# ADC.net
KiCad netlist of a schematic drawn in Altium Designer
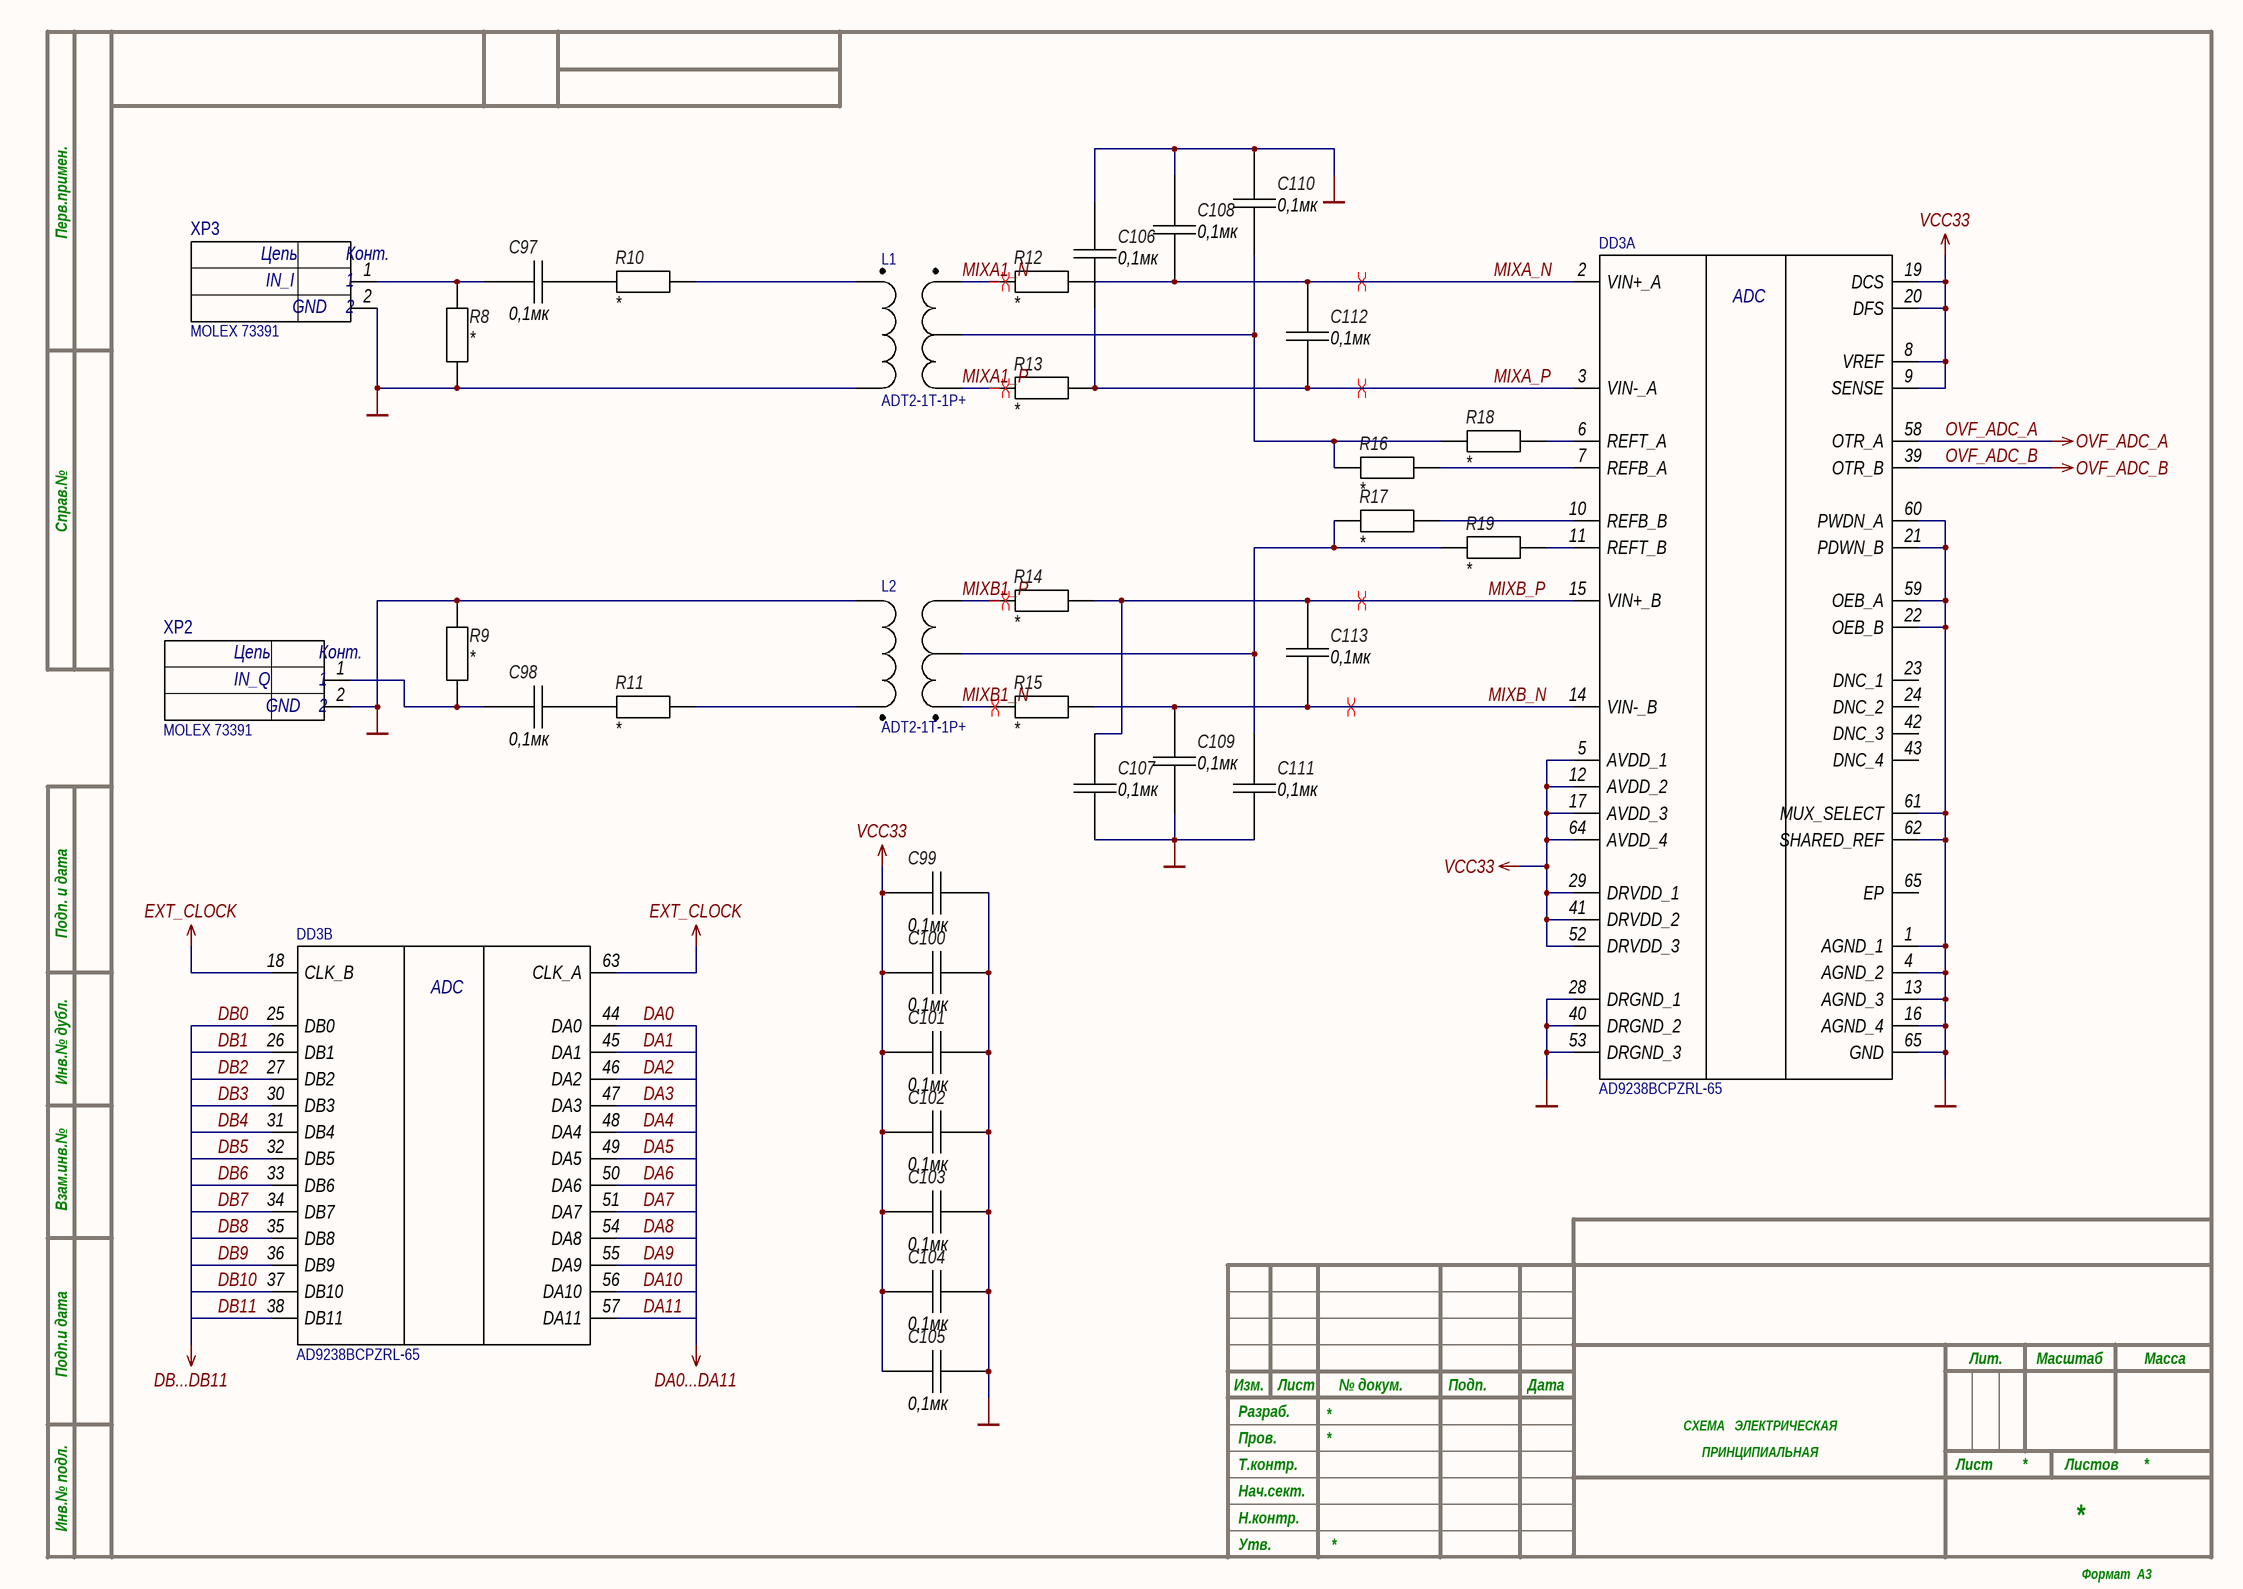
[diagram p0: ADC.SchDoc]

(export (version "E")
  (design (tool "Eeschema 10.0.6"))
  (components
    (comp (ref "C97")
      (value "0,1мк")
      (footprint "0603")
      (libsource (lib "FPGA_Automotibe_Radar_Lib") (part "Capacitor_0603"))
    )
    (comp (ref "C98")
      (value "0,1мк")
      (footprint "0603")
      (libsource (lib "FPGA_Automotibe_Radar_Lib") (part "Capacitor_0603"))
    )
    (comp (ref "C99")
      (value "0,1мк")
      (footprint "RESC1005X35N")
      (libsource (lib "FPGA_Automotibe_Radar_Lib") (part "Capacitor_0.1u"))
    )
    (comp (ref "C100")
      (value "0,1мк")
      (footprint "RESC1005X35N")
      (libsource (lib "FPGA_Automotibe_Radar_Lib") (part "Capacitor_0.1u"))
    )
    (comp (ref "C101")
      (value "0,1мк")
      (footprint "RESC1005X35N")
      (libsource (lib "FPGA_Automotibe_Radar_Lib") (part "Capacitor_0.1u"))
    )
    (comp (ref "C102")
      (value "0,1мк")
      (footprint "RESC1005X35N")
      (libsource (lib "FPGA_Automotibe_Radar_Lib") (part "Capacitor_0.1u"))
    )
    (comp (ref "C103")
      (value "0,1мк")
      (footprint "RESC1005X35N")
      (libsource (lib "FPGA_Automotibe_Radar_Lib") (part "Capacitor_0.1u"))
    )
    (comp (ref "C104")
      (value "0,1мк")
      (footprint "RESC1005X35N")
      (libsource (lib "FPGA_Automotibe_Radar_Lib") (part "Capacitor_0.1u"))
    )
    (comp (ref "C105")
      (value "0,1мк")
      (footprint "RESC1005X35N")
      (libsource (lib "FPGA_Automotibe_Radar_Lib") (part "Capacitor_0.1u"))
    )
    (comp (ref "C106")
      (value "0,1мк")
      (footprint "0603")
      (libsource (lib "FPGA_Automotibe_Radar_Lib") (part "Capacitor_0603"))
    )
    (comp (ref "C107")
      (value "0,1мк")
      (footprint "0603")
      (libsource (lib "FPGA_Automotibe_Radar_Lib") (part "Capacitor_0603"))
    )
    (comp (ref "C108")
      (value "0,1мк")
      (footprint "0603")
      (libsource (lib "FPGA_Automotibe_Radar_Lib") (part "Capacitor_0603"))
    )
    (comp (ref "C109")
      (value "0,1мк")
      (footprint "0603")
      (libsource (lib "FPGA_Automotibe_Radar_Lib") (part "Capacitor_0603"))
    )
    (comp (ref "C110")
      (value "0,1мк")
      (footprint "0603")
      (libsource (lib "FPGA_Automotibe_Radar_Lib") (part "Capacitor_0603"))
    )
    (comp (ref "C111")
      (value "0,1мк")
      (footprint "0603")
      (libsource (lib "FPGA_Automotibe_Radar_Lib") (part "Capacitor_0603"))
    )
    (comp (ref "C112")
      (value "0,1мк")
      (footprint "RESC1005X35N")
      (libsource (lib "FPGA_Automotibe_Radar_Lib") (part "Capacitor_0.1u"))
    )
    (comp (ref "C113")
      (value "0,1мк")
      (footprint "RESC1005X35N")
      (libsource (lib "FPGA_Automotibe_Radar_Lib") (part "Capacitor_0.1u"))
    )
    (comp (ref "DD3")
      (value "AD9238BCPZRL-65")
      (footprint "QFN50P900X900X80-65N-D")
      (libsource (lib "FPGA_Automotibe_Radar_Lib") (part "ADC"))
    )
    (comp (ref "L1") (value "ADT2-1T-1P+") (footprint "ADT1517") (libsource (lib "") (part "TRANSFORMER_1")))
    (comp (ref "L2")
      (value "ADT2-1T-1P+")
      (footprint "ADT1517")
      (libsource (lib "FPGA_Automotibe_Radar_Lib") (part "TRANSFORMER"))
    )
    (comp (ref "R8")
      (value "*")
      (footprint "RESC3216X75N")
      (fields
        (field (name "TOLERANCE") "5%")
        (field (name "POWER") "0,1 Вт")
        (field (name "VALUEMANUFACTURERPARTNUMBER") "RC0603JR-07680RL")
      )
      (libsource (lib "FPGA_Automotibe_Radar_Lib") (part "Resistor"))
    )
    (comp (ref "R9")
      (value "*")
      (footprint "RESC3216X75N")
      (fields
        (field (name "TOLERANCE") "5%")
        (field (name "POWER") "0,1 Вт")
        (field (name "VALUEMANUFACTURERPARTNUMBER") "RC0603JR-07680RL")
      )
      (libsource (lib "FPGA_Automotibe_Radar_Lib") (part "Resistor"))
    )
    (comp (ref "R10")
      (value "*")
      (footprint "RESC3216X75N")
      (fields
        (field (name "TOLERANCE") "5%")
        (field (name "POWER") "0,1 Вт")
        (field (name "VALUEMANUFACTURERPARTNUMBER") "RC0603JR-07680RL")
      )
      (libsource (lib "FPGA_Automotibe_Radar_Lib") (part "Resistor"))
    )
    (comp (ref "R11")
      (value "*")
      (footprint "RESC3216X75N")
      (fields
        (field (name "TOLERANCE") "5%")
        (field (name "POWER") "0,1 Вт")
        (field (name "VALUEMANUFACTURERPARTNUMBER") "RC0603JR-07680RL")
      )
      (libsource (lib "FPGA_Automotibe_Radar_Lib") (part "Resistor"))
    )
    (comp (ref "R12")
      (value "*")
      (footprint "RESC3216X75N")
      (fields
        (field (name "TOLERANCE") "5%")
        (field (name "POWER") "0,1 Вт")
        (field (name "VALUEMANUFACTURERPARTNUMBER") "RC0603JR-07680RL")
      )
      (libsource (lib "FPGA_Automotibe_Radar_Lib") (part "Resistor"))
    )
    (comp (ref "R13")
      (value "*")
      (footprint "RESC3216X75N")
      (fields
        (field (name "TOLERANCE") "5%")
        (field (name "POWER") "0,1 Вт")
        (field (name "VALUEMANUFACTURERPARTNUMBER") "RC0603JR-07680RL")
      )
      (libsource (lib "FPGA_Automotibe_Radar_Lib") (part "Resistor"))
    )
    (comp (ref "R14")
      (value "*")
      (footprint "RESC3216X75N")
      (fields
        (field (name "TOLERANCE") "5%")
        (field (name "POWER") "0,1 Вт")
        (field (name "VALUEMANUFACTURERPARTNUMBER") "RC0603JR-07680RL")
      )
      (libsource (lib "FPGA_Automotibe_Radar_Lib") (part "Resistor"))
    )
    (comp (ref "R15")
      (value "*")
      (footprint "RESC3216X75N")
      (fields
        (field (name "TOLERANCE") "5%")
        (field (name "POWER") "0,1 Вт")
        (field (name "VALUEMANUFACTURERPARTNUMBER") "RC0603JR-07680RL")
      )
      (libsource (lib "FPGA_Automotibe_Radar_Lib") (part "Resistor"))
    )
    (comp (ref "R16")
      (value "*")
      (footprint "RESC3216X75N")
      (fields
        (field (name "TOLERANCE") "5%")
        (field (name "POWER") "0,1 Вт")
        (field (name "VALUEMANUFACTURERPARTNUMBER") "RC0603JR-07680RL")
      )
      (libsource (lib "FPGA_Automotibe_Radar_Lib") (part "Resistor_0402_1k"))
    )
    (comp (ref "R17")
      (value "*")
      (footprint "RESC3216X75N")
      (fields
        (field (name "TOLERANCE") "5%")
        (field (name "POWER") "0,1 Вт")
        (field (name "VALUEMANUFACTURERPARTNUMBER") "RC0603JR-07680RL")
      )
      (libsource (lib "FPGA_Automotibe_Radar_Lib") (part "Resistor_0402_1k"))
    )
    (comp (ref "R18")
      (value "*")
      (footprint "RESC3216X75N")
      (fields
        (field (name "TOLERANCE") "5%")
        (field (name "POWER") "0,1 Вт")
        (field (name "VALUEMANUFACTURERPARTNUMBER") "RC0603JR-07680RL")
      )
      (libsource (lib "FPGA_Automotibe_Radar_Lib") (part "Resistor_0402_1k"))
    )
    (comp (ref "R19")
      (value "*")
      (footprint "RESC3216X75N")
      (fields
        (field (name "TOLERANCE") "5%")
        (field (name "POWER") "0,1 Вт")
        (field (name "VALUEMANUFACTURERPARTNUMBER") "RC0603JR-07680RL")
      )
      (libsource (lib "FPGA_Automotibe_Radar_Lib") (part "Resistor_0402_1k"))
    )
    (comp (ref "XP2")
      (value "MOLEX 73391")
      (footprint "CONN_73391-0070_MOL")
      (libsource (lib "FPGA_Automotibe_Radar_Lib") (part "SMA_REAL"))
    )
    (comp (ref "XP3")
      (value "MOLEX 73391")
      (footprint "CONN_73391-0070_MOL")
      (libsource (lib "FPGA_Automotibe_Radar_Lib") (part "SMA_REAL"))
    )
  )
  (nets
    (net (code "1") (name "/DA0") (class "Default")
      (node (ref "DD3") (pin "44") (pinfunction "DA0_44") (pintype "passive"))
    )
    (net (code "2") (name "/DA1") (class "Default")
      (node (ref "DD3") (pin "45") (pinfunction "DA1_45") (pintype "passive"))
    )
    (net (code "3") (name "/DA2") (class "Default")
      (node (ref "DD3") (pin "46") (pinfunction "DA2_46") (pintype "passive"))
    )
    (net (code "4") (name "/DA3") (class "Default")
      (node (ref "DD3") (pin "47") (pinfunction "DA3_47") (pintype "passive"))
    )
    (net (code "5") (name "/DA4") (class "Default")
      (node (ref "DD3") (pin "48") (pinfunction "DA4_48") (pintype "passive"))
    )
    (net (code "6") (name "/DA5") (class "Default")
      (node (ref "DD3") (pin "49") (pinfunction "DA5_49") (pintype "passive"))
    )
    (net (code "7") (name "/DA6") (class "Default")
      (node (ref "DD3") (pin "50") (pinfunction "DA6_50") (pintype "passive"))
    )
    (net (code "8") (name "/DA7") (class "Default")
      (node (ref "DD3") (pin "51") (pinfunction "DA7_51") (pintype "passive"))
    )
    (net (code "9") (name "/DA8") (class "Default")
      (node (ref "DD3") (pin "54") (pinfunction "DA8_54") (pintype "passive"))
    )
    (net (code "10") (name "/DA9") (class "Default")
      (node (ref "DD3") (pin "55") (pinfunction "DA9_55") (pintype "passive"))
    )
    (net (code "11") (name "/DA10") (class "Default")
      (node (ref "DD3") (pin "56") (pinfunction "DA10_56") (pintype "passive"))
    )
    (net (code "12") (name "/DA11") (class "Default")
      (node (ref "DD3") (pin "57") (pinfunction "DA11_57") (pintype "passive"))
    )
    (net (code "13") (name "/DB0") (class "Default")
      (node (ref "DD3") (pin "25") (pinfunction "DB0_25") (pintype "passive"))
    )
    (net (code "14") (name "/DB1") (class "Default")
      (node (ref "DD3") (pin "26") (pinfunction "DB1_26") (pintype "passive"))
    )
    (net (code "15") (name "/DB2") (class "Default")
      (node (ref "DD3") (pin "27") (pinfunction "DB2_27") (pintype "passive"))
    )
    (net (code "16") (name "/DB3") (class "Default")
      (node (ref "DD3") (pin "30") (pinfunction "DB3_30") (pintype "passive"))
    )
    (net (code "17") (name "/DB4") (class "Default")
      (node (ref "DD3") (pin "31") (pinfunction "DB4_31") (pintype "passive"))
    )
    (net (code "18") (name "/DB5") (class "Default")
      (node (ref "DD3") (pin "32") (pinfunction "DB5_32") (pintype "passive"))
    )
    (net (code "19") (name "/DB6") (class "Default")
      (node (ref "DD3") (pin "33") (pinfunction "DB6_33") (pintype "passive"))
    )
    (net (code "20") (name "/DB7") (class "Default")
      (node (ref "DD3") (pin "34") (pinfunction "DB7_34") (pintype "passive"))
    )
    (net (code "21") (name "/DB8") (class "Default")
      (node (ref "DD3") (pin "35") (pinfunction "DB8_35") (pintype "passive"))
    )
    (net (code "22") (name "/DB9") (class "Default")
      (node (ref "DD3") (pin "36") (pinfunction "DB9_36") (pintype "passive"))
    )
    (net (code "23") (name "/DB10") (class "Default")
      (node (ref "DD3") (pin "37") (pinfunction "DB10_37") (pintype "passive"))
    )
    (net (code "24") (name "/DB11") (class "Default")
      (node (ref "DD3") (pin "38") (pinfunction "DB11_38") (pintype "passive"))
    )
    (net (code "25") (name "/MIXA1_N") (class "Default")
      (node (ref "L1") (pin "6") (pinfunction "6_6") (pintype "passive"))
      (node (ref "R12") (pin "1") (pinfunction "1_1") (pintype "passive"))
    )
    (net (code "26") (name "/MIXA1_P") (class "Default")
      (node (ref "L1") (pin "4") (pinfunction "4_4") (pintype "passive"))
      (node (ref "R13") (pin "1") (pinfunction "1_1") (pintype "passive"))
    )
    (net (code "27") (name "/MIXA_N") (class "Default")
      (node (ref "C108") (pin "2") (pinfunction "2_2") (pintype "passive"))
      (node (ref "C112") (pin "1") (pinfunction "1_1") (pintype "passive"))
      (node (ref "DD3") (pin "2") (pinfunction "VIN+_A_2") (pintype "passive"))
      (node (ref "R12") (pin "2") (pinfunction "2_2") (pintype "passive"))
    )
    (net (code "28") (name "/MIXA_P") (class "Default")
      (node (ref "C106") (pin "1") (pinfunction "1_1") (pintype "passive"))
      (node (ref "C112") (pin "2") (pinfunction "2_2") (pintype "passive"))
      (node (ref "DD3") (pin "3") (pinfunction "VIN-_A_3") (pintype "passive"))
      (node (ref "R13") (pin "2") (pinfunction "2_2") (pintype "passive"))
    )
    (net (code "29") (name "/MIXB1_N") (class "Default")
      (node (ref "L2") (pin "6") (pinfunction "6_6") (pintype "passive"))
      (node (ref "R15") (pin "1") (pinfunction "1_1") (pintype "passive"))
    )
    (net (code "30") (name "/MIXB1_P") (class "Default")
      (node (ref "L2") (pin "4") (pinfunction "4_4") (pintype "passive"))
      (node (ref "R14") (pin "1") (pinfunction "1_1") (pintype "passive"))
    )
    (net (code "31") (name "/MIXB_N") (class "Default")
      (node (ref "C109") (pin "1") (pinfunction "1_1") (pintype "passive"))
      (node (ref "C113") (pin "1") (pinfunction "1_1") (pintype "passive"))
      (node (ref "DD3") (pin "14") (pinfunction "VIN-_B_14") (pintype "passive"))
      (node (ref "R15") (pin "2") (pinfunction "2_2") (pintype "passive"))
    )
    (net (code "32") (name "/MIXB_P") (class "Default")
      (node (ref "C107") (pin "1") (pinfunction "1_1") (pintype "passive"))
      (node (ref "C113") (pin "2") (pinfunction "2_2") (pintype "passive"))
      (node (ref "DD3") (pin "15") (pinfunction "VIN+_B_15") (pintype "passive"))
      (node (ref "R14") (pin "2") (pinfunction "2_2") (pintype "passive"))
    )
    (net (code "35") (name "EXT_CLOCK") (class "Default")
      (node (ref "DD3") (pin "18") (pinfunction "CLK_B_18") (pintype "passive"))
      (node (ref "DD3") (pin "63") (pinfunction "CLK_A_63") (pintype "passive"))
    )
    (net (code "36") (name "GND") (class "Default")
      (node (ref "C100") (pin "2") (pinfunction "2_2") (pintype "passive"))
      (node (ref "C101") (pin "2") (pinfunction "2_2") (pintype "passive"))
      (node (ref "C102") (pin "2") (pinfunction "2_2") (pintype "passive"))
      (node (ref "C103") (pin "2") (pinfunction "2_2") (pintype "passive"))
      (node (ref "C104") (pin "2") (pinfunction "2_2") (pintype "passive"))
      (node (ref "C105") (pin "2") (pinfunction "2_2") (pintype "passive"))
      (node (ref "C106") (pin "2") (pinfunction "2_2") (pintype "passive"))
      (node (ref "C107") (pin "2") (pinfunction "2_2") (pintype "passive"))
      (node (ref "C108") (pin "1") (pinfunction "1_1") (pintype "passive"))
      (node (ref "C109") (pin "2") (pinfunction "2_2") (pintype "passive"))
      (node (ref "C110") (pin "1") (pinfunction "1_1") (pintype "passive"))
      (node (ref "C111") (pin "2") (pinfunction "2_2") (pintype "passive"))
      (node (ref "C99") (pin "2") (pinfunction "2_2") (pintype "passive"))
      (node (ref "DD3") (pin "1") (pinfunction "AGND_1_1") (pintype "passive"))
      (node (ref "DD3") (pin "13") (pinfunction "AGND_3_13") (pintype "passive"))
      (node (ref "DD3") (pin "16") (pinfunction "AGND_4_16") (pintype "passive"))
      (node (ref "DD3") (pin "21") (pinfunction "PDWN_B_21") (pintype "passive"))
      (node (ref "DD3") (pin "22") (pinfunction "OEB_B_22") (pintype "passive"))
      (node (ref "DD3") (pin "28") (pinfunction "DRGND_1_28") (pintype "passive"))
      (node (ref "DD3") (pin "4") (pinfunction "AGND_2_4") (pintype "passive"))
      (node (ref "DD3") (pin "40") (pinfunction "DRGND_2_40") (pintype "passive"))
      (node (ref "DD3") (pin "53") (pinfunction "DRGND_3_53") (pintype "passive"))
      (node (ref "DD3") (pin "59") (pinfunction "OEB_A_59") (pintype "passive"))
      (node (ref "DD3") (pin "60") (pinfunction "PWDN_A_60") (pintype "passive"))
      (node (ref "DD3") (pin "61") (pinfunction "MUX_SELECT_61") (pintype "passive"))
      (node (ref "DD3") (pin "62") (pinfunction "SHARED_REF_62") (pintype "passive"))
      (node (ref "DD3") (pin "65") (pinfunction "GND_65") (pintype "passive"))
      (node (ref "L1") (pin "2") (pinfunction "2_2") (pintype "passive"))
      (node (ref "L2") (pin "2") (pinfunction "2_2") (pintype "passive"))
      (node (ref "R8") (pin "1") (pinfunction "1_1") (pintype "passive"))
      (node (ref "R9") (pin "1") (pinfunction "1_1") (pintype "passive"))
      (node (ref "XP2") (pin "2") (pinfunction "2_2") (pintype "passive"))
      (node (ref "XP3") (pin "2") (pinfunction "2_2") (pintype "passive"))
    )
    (net (code "37") (name "Net-(C97-Pad1)") (class "Default")
      (node (ref "C97") (pin "1") (pinfunction "1_1") (pintype "passive"))
      (node (ref "R8") (pin "2") (pinfunction "2_2") (pintype "passive"))
      (node (ref "XP3") (pin "1") (pinfunction "1_1") (pintype "passive"))
    )
    (net (code "38") (name "Net-(C97-Pad2)") (class "Default")
      (node (ref "C97") (pin "2") (pinfunction "2_2") (pintype "passive"))
      (node (ref "R10") (pin "1") (pinfunction "1_1") (pintype "passive"))
    )
    (net (code "39") (name "Net-(C98-Pad1)") (class "Default")
      (node (ref "C98") (pin "1") (pinfunction "1_1") (pintype "passive"))
      (node (ref "R9") (pin "2") (pinfunction "2_2") (pintype "passive"))
      (node (ref "XP2") (pin "1") (pinfunction "1_1") (pintype "passive"))
    )
    (net (code "40") (name "Net-(C98-Pad2)") (class "Default")
      (node (ref "C98") (pin "2") (pinfunction "2_2") (pintype "passive"))
      (node (ref "R11") (pin "1") (pinfunction "1_1") (pintype "passive"))
    )
    (net (code "41") (name "Net-(C110-Pad2)") (class "Default")
      (node (ref "C110") (pin "2") (pinfunction "2_2") (pintype "passive"))
      (node (ref "L1") (pin "5") (pinfunction "5_5") (pintype "passive"))
      (node (ref "R16") (pin "1") (pinfunction "1_1") (pintype "passive"))
      (node (ref "R18") (pin "1") (pinfunction "1_1") (pintype "passive"))
    )
    (net (code "42") (name "Net-(C111-Pad1)") (class "Default")
      (node (ref "C111") (pin "1") (pinfunction "1_1") (pintype "passive"))
      (node (ref "L2") (pin "5") (pinfunction "5_5") (pintype "passive"))
      (node (ref "R17") (pin "1") (pinfunction "1_1") (pintype "passive"))
      (node (ref "R19") (pin "1") (pinfunction "1_1") (pintype "passive"))
    )
    (net (code "43") (name "Net-(DD3A-REFB_A)") (class "Default")
      (node (ref "DD3") (pin "7") (pinfunction "REFB_A_7") (pintype "passive"))
      (node (ref "R16") (pin "2") (pinfunction "2_2") (pintype "passive"))
    )
    (net (code "44") (name "Net-(DD3A-REFB_B)") (class "Default")
      (node (ref "DD3") (pin "10") (pinfunction "REFB_B_10") (pintype "passive"))
      (node (ref "R17") (pin "2") (pinfunction "2_2") (pintype "passive"))
    )
    (net (code "45") (name "Net-(DD3A-REFT_A)") (class "Default")
      (node (ref "DD3") (pin "6") (pinfunction "REFT_A_6") (pintype "passive"))
      (node (ref "R18") (pin "2") (pinfunction "2_2") (pintype "passive"))
    )
    (net (code "46") (name "Net-(DD3A-REFT_B)") (class "Default")
      (node (ref "DD3") (pin "11") (pinfunction "REFT_B_11") (pintype "passive"))
      (node (ref "R19") (pin "2") (pinfunction "2_2") (pintype "passive"))
    )
    (net (code "47") (name "Net-(L1-Pad1)") (class "Default")
      (node (ref "L1") (pin "1") (pinfunction "1_1") (pintype "passive"))
      (node (ref "R10") (pin "2") (pinfunction "2_2") (pintype "passive"))
    )
    (net (code "48") (name "Net-(L2-Pad1)") (class "Default")
      (node (ref "L2") (pin "1") (pinfunction "1_1") (pintype "passive"))
      (node (ref "R11") (pin "2") (pinfunction "2_2") (pintype "passive"))
    )
    (net (code "49") (name "OVF_ADC_A") (class "Default")
      (node (ref "DD3") (pin "58") (pinfunction "OTR_A_58") (pintype "passive"))
    )
    (net (code "50") (name "OVF_ADC_B") (class "Default")
      (node (ref "DD3") (pin "39") (pinfunction "OTR_B_39") (pintype "passive"))
    )
    (net (code "51") (name "VCC33") (class "Default")
      (node (ref "C100") (pin "1") (pinfunction "1_1") (pintype "passive"))
      (node (ref "C101") (pin "1") (pinfunction "1_1") (pintype "passive"))
      (node (ref "C102") (pin "1") (pinfunction "1_1") (pintype "passive"))
      (node (ref "C103") (pin "1") (pinfunction "1_1") (pintype "passive"))
      (node (ref "C104") (pin "1") (pinfunction "1_1") (pintype "passive"))
      (node (ref "C105") (pin "1") (pinfunction "1_1") (pintype "passive"))
      (node (ref "C99") (pin "1") (pinfunction "1_1") (pintype "passive"))
      (node (ref "DD3") (pin "12") (pinfunction "AVDD_2_12") (pintype "passive"))
      (node (ref "DD3") (pin "17") (pinfunction "AVDD_3_17") (pintype "passive"))
      (node (ref "DD3") (pin "19") (pinfunction "DCS_19") (pintype "passive"))
      (node (ref "DD3") (pin "20") (pinfunction "DFS_20") (pintype "passive"))
      (node (ref "DD3") (pin "29") (pinfunction "DRVDD_1_29") (pintype "passive"))
      (node (ref "DD3") (pin "41") (pinfunction "DRVDD_2_41") (pintype "passive"))
      (node (ref "DD3") (pin "5") (pinfunction "AVDD_1_5") (pintype "passive"))
      (node (ref "DD3") (pin "52") (pinfunction "DRVDD_3_52") (pintype "passive"))
      (node (ref "DD3") (pin "64") (pinfunction "AVDD_4_64") (pintype "passive"))
      (node (ref "DD3") (pin "8") (pinfunction "VREF_8") (pintype "passive"))
      (node (ref "DD3") (pin "9") (pinfunction "SENSE_9") (pintype "passive"))
    )
    (net (code "52") (name "unconnected-(DD3A-DNC_1-Pad23)") (class "Default")
      (node (ref "DD3") (pin "23") (pinfunction "DNC_1_23") (pintype "passive"))
    )
    (net (code "53") (name "unconnected-(DD3A-DNC_2-Pad24)") (class "Default")
      (node (ref "DD3") (pin "24") (pinfunction "DNC_2_24") (pintype "passive"))
    )
    (net (code "54") (name "unconnected-(DD3A-DNC_3-Pad42)") (class "Default")
      (node (ref "DD3") (pin "42") (pinfunction "DNC_3_42") (pintype "passive"))
    )
    (net (code "55") (name "unconnected-(DD3A-DNC_4-Pad43)") (class "Default")
      (node (ref "DD3") (pin "43") (pinfunction "DNC_4_43") (pintype "passive"))
    )
    (net (code "56") (name "unconnected-(DD3A-EP-Pad65)") (class "Default")
      (node (ref "DD3") (pin "65") (pinfunction "EP_65") (pintype "passive"))
    )
  )
)
